# Relay_5x.net
KiCad netlist of a schematic drawn in EasyEDA Pro
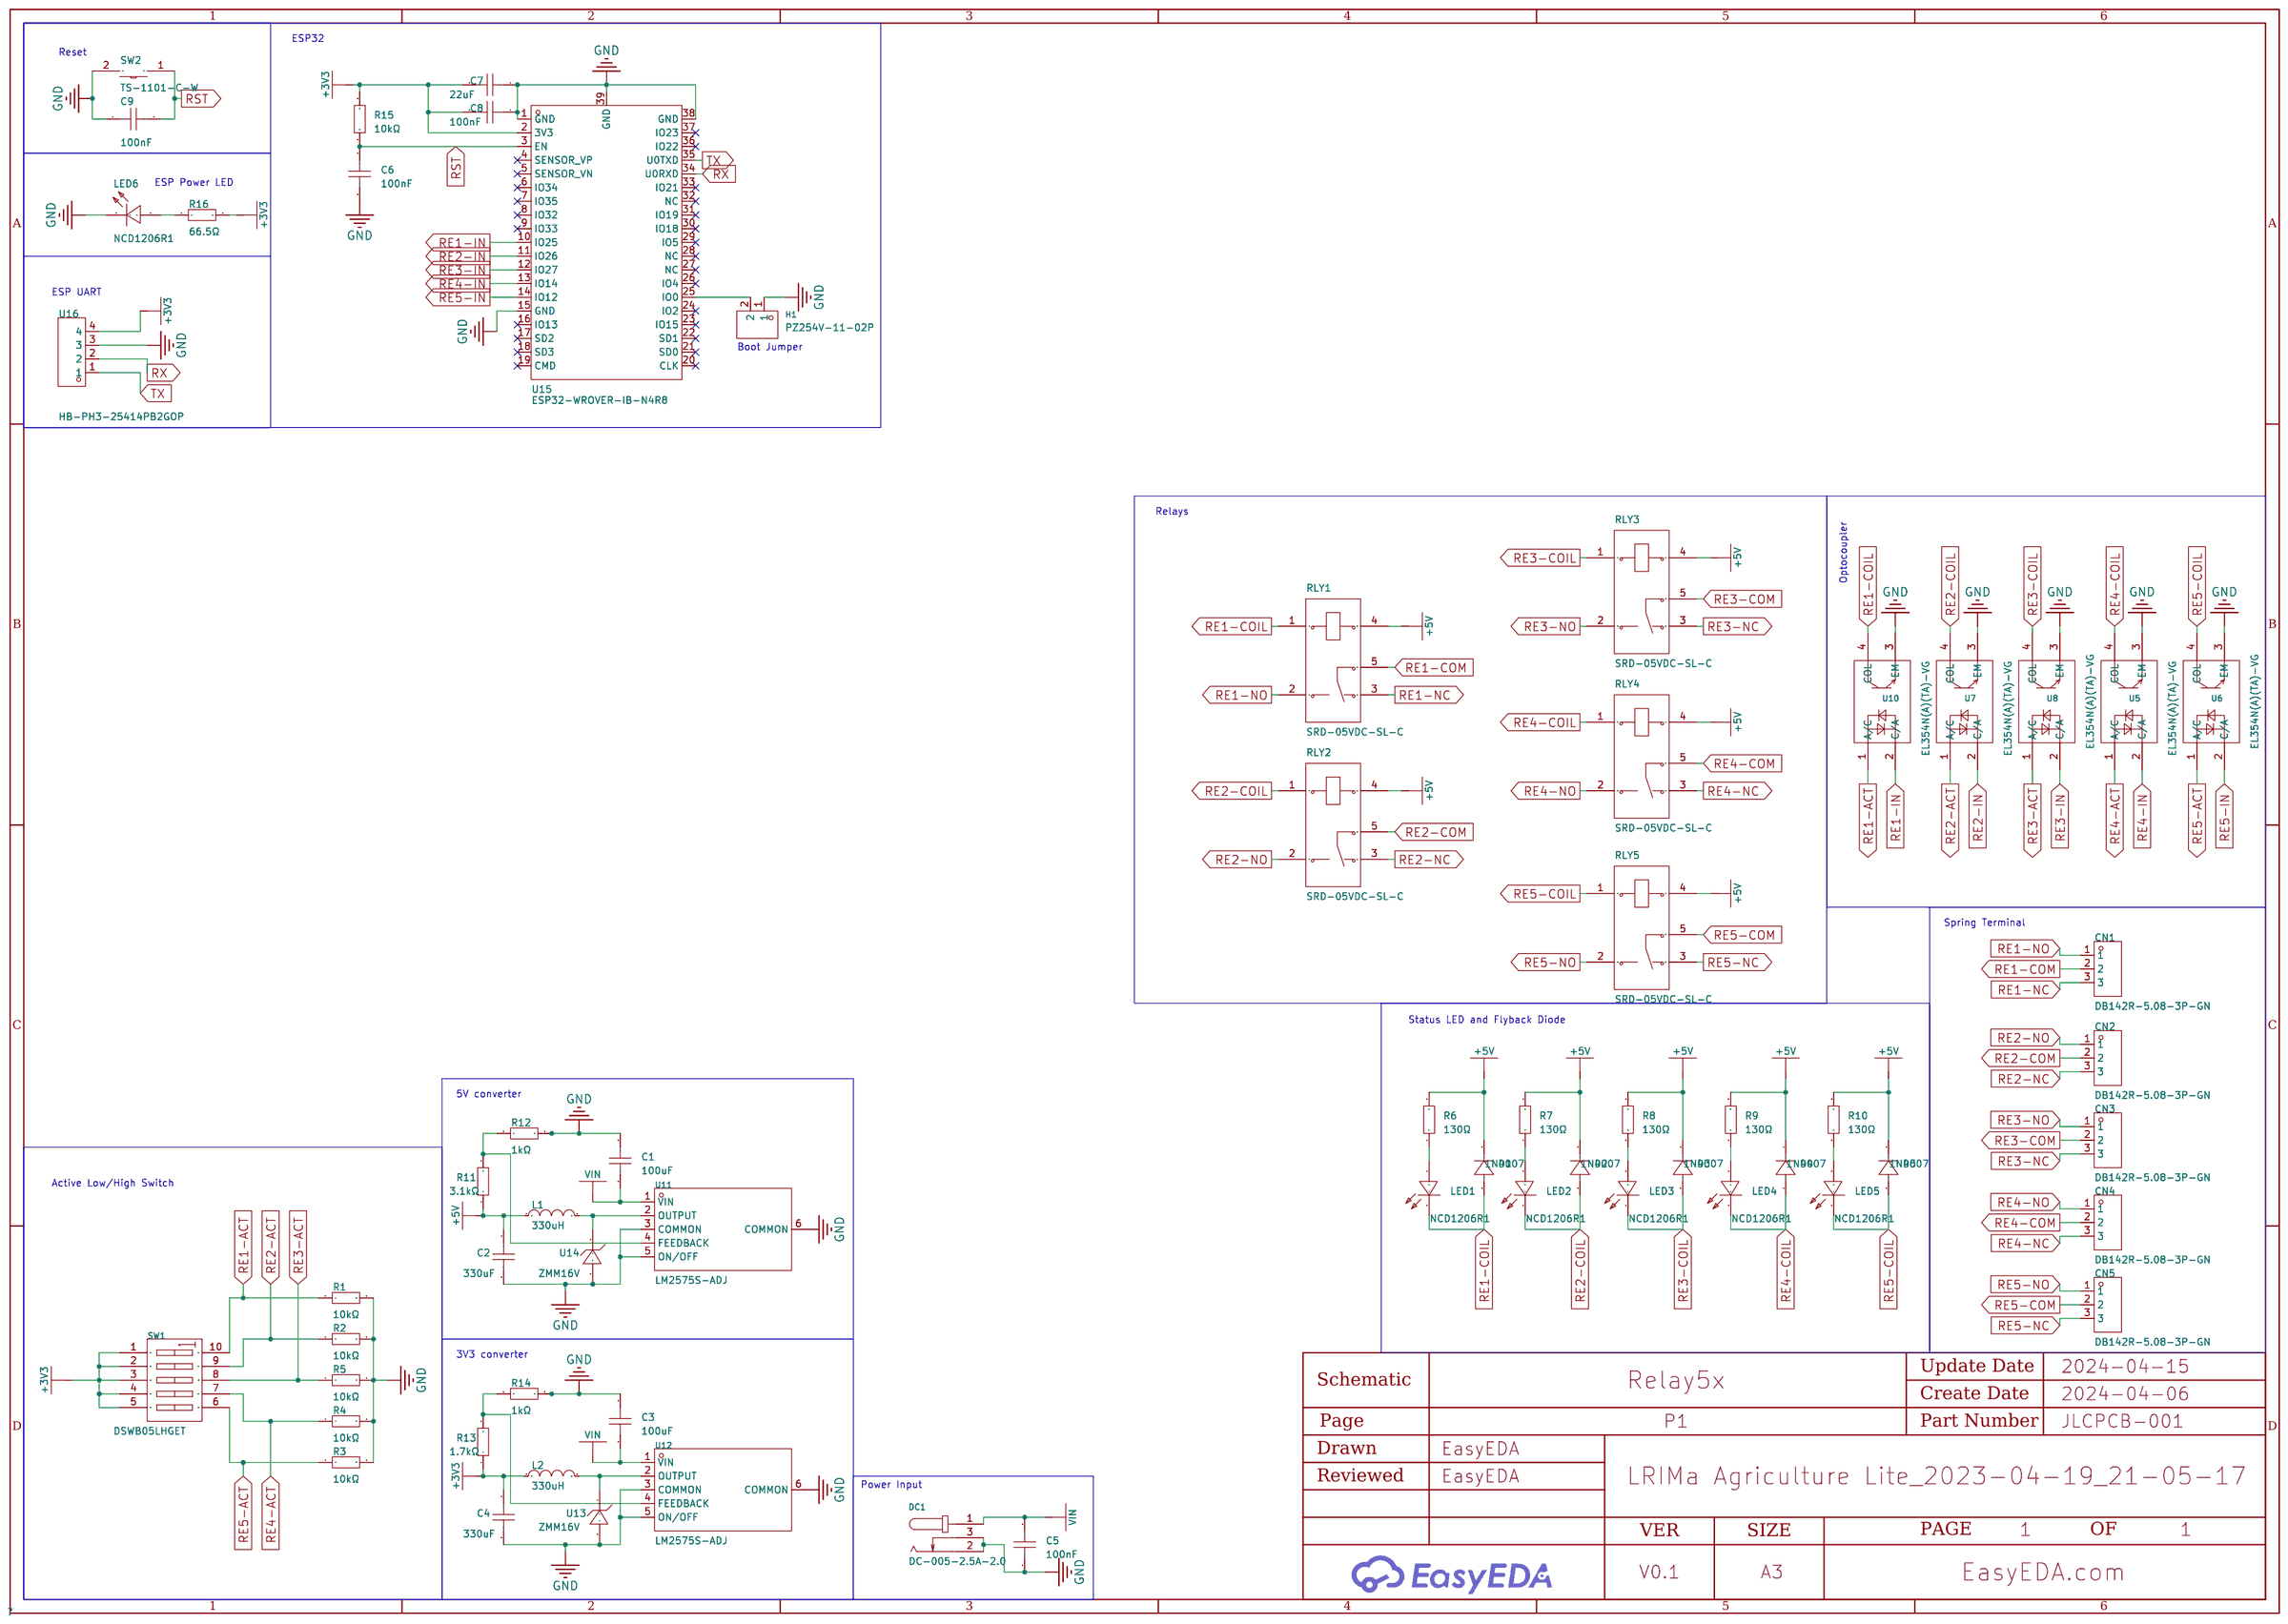
[diagram p0: schematic sheet]

(export (version "E")
  (design (tool "Eeschema 10.0.6"))
  (components
    (comp (ref "C1")
      (value "100uF")
      (fields
        (field (name "Manufacturer Part") "CL31A107MQHNNNE")
        (field (name "Manufacturer") "SAMSUNG(三星)")
      )
      (libsource (lib "easyedapro") (part "CAP"))
    )
    (comp (ref "C2")
      (value "330uF")
      (fields
        (field (name "Manufacturer Part") "GRM32ER60G337ME05L")
        (field (name "Manufacturer") "muRata(村田)")
      )
      (libsource (lib "easyedapro") (part "CAP"))
    )
    (comp (ref "C3")
      (value "100uF")
      (fields
        (field (name "Manufacturer Part") "CL31A107MQHNNNE")
        (field (name "Manufacturer") "SAMSUNG(三星)")
      )
      (libsource (lib "easyedapro") (part "CAP"))
    )
    (comp (ref "C4")
      (value "330uF")
      (fields
        (field (name "Manufacturer Part") "GRM32ER60G337ME05L")
        (field (name "Manufacturer") "muRata(村田)")
      )
      (libsource (lib "easyedapro") (part "CAP"))
    )
    (comp (ref "C5")
      (value "100nF")
      (fields (field (name "Manufacturer Part") "1206B104K101NT") (field (name "Manufacturer") "FH(风华)"))
      (libsource (lib "easyedapro") (part "CAP"))
    )
    (comp (ref "C6")
      (value "100nF")
      (fields (field (name "Manufacturer Part") "1206B104K101NT") (field (name "Manufacturer") "FH(风华)"))
      (libsource (lib "easyedapro") (part "CAP"))
    )
    (comp (ref "C7")
      (value "22uF")
      (fields
        (field (name "Manufacturer Part") "CL31A226KOHNNNE")
        (field (name "Manufacturer") "SAMSUNG(三星)")
      )
      (libsource (lib "easyedapro") (part "CAP"))
    )
    (comp (ref "C8")
      (value "100nF")
      (fields (field (name "Manufacturer Part") "1206B104K101NT") (field (name "Manufacturer") "FH(风华)"))
      (libsource (lib "easyedapro") (part "CAP"))
    )
    (comp (ref "C9")
      (value "100nF")
      (fields (field (name "Manufacturer Part") "1206B104K101NT") (field (name "Manufacturer") "FH(风华)"))
      (libsource (lib "easyedapro") (part "CAP"))
    )
    (comp (ref "CN1")
      (value "DB142R-5.08-3P-GN")
      (footprint "easyedapro:CONN-TH_3P-P5.08_DIBO_DB142R-5.08-3P")
      (fields (field (name "Manufacturer") "DORABO(地博电气)"))
      (libsource (lib "easyedapro") (part "DB142R-5.08-3P"))
    )
    (comp (ref "CN2")
      (value "DB142R-5.08-3P-GN")
      (footprint "easyedapro:CONN-TH_3P-P5.08_DIBO_DB142R-5.08-3P")
      (fields (field (name "Manufacturer") "DORABO(地博电气)"))
      (libsource (lib "easyedapro") (part "DB142R-5.08-3P"))
    )
    (comp (ref "CN3")
      (value "DB142R-5.08-3P-GN")
      (footprint "easyedapro:CONN-TH_3P-P5.08_DIBO_DB142R-5.08-3P")
      (fields (field (name "Manufacturer") "DORABO(地博电气)"))
      (libsource (lib "easyedapro") (part "DB142R-5.08-3P"))
    )
    (comp (ref "CN4")
      (value "DB142R-5.08-3P-GN")
      (footprint "easyedapro:CONN-TH_3P-P5.08_DIBO_DB142R-5.08-3P")
      (fields (field (name "Manufacturer") "DORABO(地博电气)"))
      (libsource (lib "easyedapro") (part "DB142R-5.08-3P"))
    )
    (comp (ref "CN5")
      (value "DB142R-5.08-3P-GN")
      (footprint "easyedapro:CONN-TH_3P-P5.08_DIBO_DB142R-5.08-3P")
      (fields (field (name "Manufacturer") "DORABO(地博电气)"))
      (libsource (lib "easyedapro") (part "DB142R-5.08-3P"))
    )
    (comp (ref "D1")
      (value "1N4007")
      (fields (field (name "Manufacturer") "GOOD-ARK(固锝)"))
      (libsource (lib "easyedapro") (part "D_1N4007"))
    )
    (comp (ref "D2")
      (value "1N4007")
      (fields (field (name "Manufacturer") "GOOD-ARK(固锝)"))
      (libsource (lib "easyedapro") (part "D_1N4007"))
    )
    (comp (ref "D3")
      (value "1N4007")
      (fields (field (name "Manufacturer") "GOOD-ARK(固锝)"))
      (libsource (lib "easyedapro") (part "D_1N4007"))
    )
    (comp (ref "D4")
      (value "1N4007")
      (fields (field (name "Manufacturer") "GOOD-ARK(固锝)"))
      (libsource (lib "easyedapro") (part "D_1N4007"))
    )
    (comp (ref "D5")
      (value "1N4007")
      (fields (field (name "Manufacturer") "GOOD-ARK(固锝)"))
      (libsource (lib "easyedapro") (part "D_1N4007"))
    )
    (comp (ref "DC1")
      (value "DC-005-2.5A-2.0")
      (footprint "easyedapro:CONN-TH_DC-005-2.5A-2.0")
      (fields (field (name "Manufacturer") "XKB Connectivity(中国星坤)"))
      (libsource (lib "easyedapro") (part "DC-005-2.5A-2.0"))
    )
    (comp (ref "H1")
      (value "PZ254V-11-02P")
      (footprint "easyedapro:HDR-TH_2P-P2.54-V-M")
      (fields (field (name "Manufacturer") "XFCN(兴飞)"))
      (libsource (lib "easyedapro") (part "PZ254V-11-02P"))
    )
    (comp (ref "L1")
      (value "330uH")
      (fields (field (name "Manufacturer Part") "NLCV32T-331K-PF") (field (name "Manufacturer") "TDK"))
      (libsource (lib "easyedapro") (part "电感"))
    )
    (comp (ref "L2")
      (value "330uH")
      (fields (field (name "Manufacturer Part") "NLCV32T-331K-PF") (field (name "Manufacturer") "TDK"))
      (libsource (lib "easyedapro") (part "电感"))
    )
    (comp (ref "LED1")
      (value "NCD1206R1")
      (footprint "easyedapro:LED1206-R-RD_RED")
      (fields (field (name "Manufacturer") "国星光电"))
      (libsource (lib "easyedapro") (part "FC-3215HRK-620D"))
    )
    (comp (ref "LED2")
      (value "NCD1206R1")
      (footprint "easyedapro:LED1206-R-RD_RED")
      (fields (field (name "Manufacturer") "国星光电"))
      (libsource (lib "easyedapro") (part "FC-3215HRK-620D"))
    )
    (comp (ref "LED3")
      (value "NCD1206R1")
      (footprint "easyedapro:LED1206-R-RD_RED")
      (fields (field (name "Manufacturer") "国星光电"))
      (libsource (lib "easyedapro") (part "FC-3215HRK-620D"))
    )
    (comp (ref "LED4")
      (value "NCD1206R1")
      (footprint "easyedapro:LED1206-R-RD_RED")
      (fields (field (name "Manufacturer") "国星光电"))
      (libsource (lib "easyedapro") (part "FC-3215HRK-620D"))
    )
    (comp (ref "LED5")
      (value "NCD1206R1")
      (footprint "easyedapro:LED1206-R-RD_RED")
      (fields (field (name "Manufacturer") "国星光电"))
      (libsource (lib "easyedapro") (part "FC-3215HRK-620D"))
    )
    (comp (ref "LED6")
      (value "NCD1206R1")
      (footprint "easyedapro:LED1206-R-RD_RED")
      (fields (field (name "Manufacturer") "国星光电"))
      (libsource (lib "easyedapro") (part "FC-3215HRK-620D"))
    )
    (comp (ref "R1")
      (value "10kΩ")
      (fields
        (field (name "Manufacturer Part") "1206W4F1002T5E")
        (field (name "Manufacturer") "UNI-ROYAL(厚声)")
      )
      (libsource (lib "easyedapro") (part "Res"))
    )
    (comp (ref "R2")
      (value "10kΩ")
      (fields
        (field (name "Manufacturer Part") "1206W4F1002T5E")
        (field (name "Manufacturer") "UNI-ROYAL(厚声)")
      )
      (libsource (lib "easyedapro") (part "Res"))
    )
    (comp (ref "R3")
      (value "10kΩ")
      (fields
        (field (name "Manufacturer Part") "1206W4F1002T5E")
        (field (name "Manufacturer") "UNI-ROYAL(厚声)")
      )
      (libsource (lib "easyedapro") (part "Res"))
    )
    (comp (ref "R4")
      (value "10kΩ")
      (fields
        (field (name "Manufacturer Part") "1206W4F1002T5E")
        (field (name "Manufacturer") "UNI-ROYAL(厚声)")
      )
      (libsource (lib "easyedapro") (part "Res"))
    )
    (comp (ref "R5")
      (value "10kΩ")
      (fields
        (field (name "Manufacturer Part") "1206W4F1002T5E")
        (field (name "Manufacturer") "UNI-ROYAL(厚声)")
      )
      (libsource (lib "easyedapro") (part "Res"))
    )
    (comp (ref "R6")
      (value "130Ω")
      (fields (field (name "Manufacturer Part") "ARG06FTC1300") (field (name "Manufacturer") "Viking(光颉)"))
      (libsource (lib "easyedapro") (part "Res"))
    )
    (comp (ref "R7")
      (value "130Ω")
      (fields (field (name "Manufacturer Part") "ARG06FTC1300") (field (name "Manufacturer") "Viking(光颉)"))
      (libsource (lib "easyedapro") (part "Res"))
    )
    (comp (ref "R8")
      (value "130Ω")
      (fields (field (name "Manufacturer Part") "ARG06FTC1300") (field (name "Manufacturer") "Viking(光颉)"))
      (libsource (lib "easyedapro") (part "Res"))
    )
    (comp (ref "R9")
      (value "130Ω")
      (fields (field (name "Manufacturer Part") "ARG06FTC1300") (field (name "Manufacturer") "Viking(光颉)"))
      (libsource (lib "easyedapro") (part "Res"))
    )
    (comp (ref "R10")
      (value "130Ω")
      (fields (field (name "Manufacturer Part") "ARG06FTC1300") (field (name "Manufacturer") "Viking(光颉)"))
      (libsource (lib "easyedapro") (part "Res"))
    )
    (comp (ref "R11")
      (value "3.1kΩ")
      (fields (field (name "Manufacturer Part") "MF1/8W-3K1±1%-ST52") (field (name "Manufacturer") "VO(翔胜)"))
      (libsource (lib "easyedapro") (part "Res"))
    )
    (comp (ref "R12")
      (value "1kΩ")
      (fields
        (field (name "Manufacturer Part") "1206W4F1001T5E")
        (field (name "Manufacturer") "UNI-ROYAL(厚声)")
      )
      (libsource (lib "easyedapro") (part "Res"))
    )
    (comp (ref "R13")
      (value "1.7kΩ")
      (fields (field (name "Manufacturer Part") "MF1/4W-1K7±1%-ST26") (field (name "Manufacturer") "VO(翔胜)"))
      (libsource (lib "easyedapro") (part "Res"))
    )
    (comp (ref "R14")
      (value "1kΩ")
      (fields
        (field (name "Manufacturer Part") "1206W4F1001T5E")
        (field (name "Manufacturer") "UNI-ROYAL(厚声)")
      )
      (libsource (lib "easyedapro") (part "Res"))
    )
    (comp (ref "R15")
      (value "10kΩ")
      (fields
        (field (name "Manufacturer Part") "1206W4F1002T5E")
        (field (name "Manufacturer") "UNI-ROYAL(厚声)")
      )
      (libsource (lib "easyedapro") (part "Res"))
    )
    (comp (ref "R16")
      (value "66.5Ω")
      (fields
        (field (name "Manufacturer Part") "CR1206F66R5P05Z")
        (field (name "Manufacturer") "EVER OHMS(天二科技)")
      )
      (libsource (lib "easyedapro") (part "Res"))
    )
    (comp (ref "RLY1")
      (value "SRD-05VDC-SL-C")
      (footprint "easyedapro:RELAY-TH_SRD-XXVDC-XL-C")
      (fields (field (name "Manufacturer") "松乐"))
      (libsource (lib "easyedapro") (part "SRD-05VDC-SL-C"))
    )
    (comp (ref "RLY2")
      (value "SRD-05VDC-SL-C")
      (footprint "easyedapro:RELAY-TH_SRD-XXVDC-XL-C")
      (fields (field (name "Manufacturer") "松乐"))
      (libsource (lib "easyedapro") (part "SRD-05VDC-SL-C"))
    )
    (comp (ref "RLY3")
      (value "SRD-05VDC-SL-C")
      (footprint "easyedapro:RELAY-TH_SRD-XXVDC-XL-C")
      (fields (field (name "Manufacturer") "松乐"))
      (libsource (lib "easyedapro") (part "SRD-05VDC-SL-C"))
    )
    (comp (ref "RLY4")
      (value "SRD-05VDC-SL-C")
      (footprint "easyedapro:RELAY-TH_SRD-XXVDC-XL-C")
      (fields (field (name "Manufacturer") "松乐"))
      (libsource (lib "easyedapro") (part "SRD-05VDC-SL-C"))
    )
    (comp (ref "RLY5")
      (value "SRD-05VDC-SL-C")
      (footprint "easyedapro:RELAY-TH_SRD-XXVDC-XL-C")
      (fields (field (name "Manufacturer") "松乐"))
      (libsource (lib "easyedapro") (part "SRD-05VDC-SL-C"))
    )
    (comp (ref "SW1")
      (value "DSWB05LHGET")
      (footprint "easyedapro:SW-TH_DSWB05LHGET")
      (description "Type:平拨,凸起式 Circuit:SPST Number of Positions:5Bit Lead Pitch:2.54mm Operating Life:- Color:Red")
      (fields (field (name "Manufacturer") "YE"))
      (libsource (lib "easyedapro") (part "DSWB05LHGET"))
    )
    (comp (ref "SW2")
      (value "TS-1101-C-W")
      (footprint "easyedapro:SW-SMD_L6.0-W3.3-LS8.0")
      (fields (field (name "Manufacturer") "XKB Connectivity(中国星坤)"))
      (libsource (lib "easyedapro") (part "TS-1101-C-W"))
    )
    (comp (ref "U5")
      (value "EL354N(A)(TA)-VG")
      (footprint "easyedapro:OPTO-SMD-4_L4.4-W4.1-P2.54-LS7.0-TL")
      (fields (field (name "Manufacturer") "EVERLIGHT(亿光)"))
      (libsource (lib "easyedapro") (part "EL354N(A)(TA)-VG"))
    )
    (comp (ref "U6")
      (value "EL354N(A)(TA)-VG")
      (footprint "easyedapro:OPTO-SMD-4_L4.4-W4.1-P2.54-LS7.0-TL")
      (fields (field (name "Manufacturer") "EVERLIGHT(亿光)"))
      (libsource (lib "easyedapro") (part "EL354N(A)(TA)-VG"))
    )
    (comp (ref "U7")
      (value "EL354N(A)(TA)-VG")
      (footprint "easyedapro:OPTO-SMD-4_L4.4-W4.1-P2.54-LS7.0-TL")
      (fields (field (name "Manufacturer") "EVERLIGHT(亿光)"))
      (libsource (lib "easyedapro") (part "EL354N(A)(TA)-VG"))
    )
    (comp (ref "U8")
      (value "EL354N(A)(TA)-VG")
      (footprint "easyedapro:OPTO-SMD-4_L4.4-W4.1-P2.54-LS7.0-TL")
      (fields (field (name "Manufacturer") "EVERLIGHT(亿光)"))
      (libsource (lib "easyedapro") (part "EL354N(A)(TA)-VG"))
    )
    (comp (ref "U10")
      (value "EL354N(A)(TA)-VG")
      (footprint "easyedapro:OPTO-SMD-4_L4.4-W4.1-P2.54-LS7.0-TL")
      (fields (field (name "Manufacturer") "EVERLIGHT(亿光)"))
      (libsource (lib "easyedapro") (part "EL354N(A)(TA)-VG"))
    )
    (comp (ref "U11")
      (value "LM2575S-ADJ")
      (footprint "easyedapro:TO-263-5_L10.2-W8.9-P1.70-BR")
      (fields (field (name "Manufacturer") "Slkor(萨科微)"))
      (libsource (lib "easyedapro") (part "LM2575S-ADJ"))
    )
    (comp (ref "U12")
      (value "LM2575S-ADJ")
      (footprint "easyedapro:TO-263-5_L10.2-W8.9-P1.70-BR")
      (fields (field (name "Manufacturer") "Slkor(萨科微)"))
      (libsource (lib "easyedapro") (part "LM2575S-ADJ"))
    )
    (comp (ref "U13")
      (value "ZMM16V")
      (footprint "easyedapro:LL-34_L3.5-W1.5-RD")
      (fields (field (name "Manufacturer") "YONGYUTAI(永裕泰)"))
      (libsource (lib "easyedapro") (part "ZMM16V"))
    )
    (comp (ref "U14")
      (value "ZMM16V")
      (footprint "easyedapro:LL-34_L3.5-W1.5-RD")
      (fields (field (name "Manufacturer") "YONGYUTAI(永裕泰)"))
      (libsource (lib "easyedapro") (part "ZMM16V"))
    )
    (comp (ref "U15")
      (value "ESP32-WROVER-IB-N4R8")
      (footprint "easyedapro:WIFI-SMD_ESP32-WROVER-IE8MB")
      (fields (field (name "Manufacturer") "ESPRESSIF(乐鑫)"))
      (libsource (lib "easyedapro") (part "ESP32-WROVER-IB-N4R8"))
    )
    (comp (ref "U16")
      (value "HB-PH3-25414PB2GOP")
      (footprint "easyedapro:HDR-TH_4P-P2.54-V-M")
      (fields (field (name "Manufacturer") "HANBO(汉博)"))
      (libsource (lib "easyedapro") (part "HB-PH3-25414PB2GOP"))
    )
  )
  (nets
    (net (code "1") (name "+3V3") (class "Default")
      (node (ref "C4") (pin "1") (pinfunction "1_1") (pintype "input"))
      (node (ref "C7") (pin "2") (pinfunction "2_2") (pintype "input"))
      (node (ref "C8") (pin "2") (pinfunction "2_2") (pintype "input"))
      (node (ref "L2") (pin "1") (pinfunction "1_1") (pintype "input"))
      (node (ref "R13") (pin "1") (pinfunction "1_1") (pintype "input"))
      (node (ref "R15") (pin "2") (pinfunction "2_2") (pintype "input"))
      (node (ref "R16") (pin "2") (pinfunction "2_2") (pintype "input"))
      (node (ref "SW1") (pin "1") (pinfunction "A1_1") (pintype "input"))
      (node (ref "SW1") (pin "2") (pinfunction "A2_2") (pintype "input"))
      (node (ref "SW1") (pin "3") (pinfunction "A3_3") (pintype "input"))
      (node (ref "SW1") (pin "4") (pinfunction "A4_4") (pintype "input"))
      (node (ref "SW1") (pin "5") (pinfunction "A5_5") (pintype "input"))
      (node (ref "U15") (pin "2") (pinfunction "3V3_2") (pintype "unspecified"))
      (node (ref "U16") (pin "4") (pinfunction "4_4") (pintype "unspecified"))
    )
    (net (code "2") (name "+5V") (class "Default")
      (node (ref "C2") (pin "1") (pinfunction "1_1") (pintype "input"))
      (node (ref "D1") (pin "1") (pinfunction "K_1") (pintype "input"))
      (node (ref "D2") (pin "1") (pinfunction "K_1") (pintype "input"))
      (node (ref "D3") (pin "1") (pinfunction "K_1") (pintype "input"))
      (node (ref "D4") (pin "1") (pinfunction "K_1") (pintype "input"))
      (node (ref "D5") (pin "1") (pinfunction "K_1") (pintype "input"))
      (node (ref "L1") (pin "1") (pinfunction "1_1") (pintype "input"))
      (node (ref "R10") (pin "2") (pinfunction "2_2") (pintype "input"))
      (node (ref "R11") (pin "1") (pinfunction "1_1") (pintype "input"))
      (node (ref "R6") (pin "2") (pinfunction "2_2") (pintype "input"))
      (node (ref "R7") (pin "2") (pinfunction "2_2") (pintype "input"))
      (node (ref "R8") (pin "2") (pinfunction "2_2") (pintype "input"))
      (node (ref "R9") (pin "2") (pinfunction "2_2") (pintype "input"))
      (node (ref "RLY1") (pin "4") (pinfunction "4_4") (pintype "input"))
      (node (ref "RLY2") (pin "4") (pinfunction "4_4") (pintype "input"))
      (node (ref "RLY3") (pin "4") (pinfunction "4_4") (pintype "input"))
      (node (ref "RLY4") (pin "4") (pinfunction "4_4") (pintype "input"))
      (node (ref "RLY5") (pin "4") (pinfunction "4_4") (pintype "input"))
    )
    (net (code "3") (name "GND") (class "Default")
      (node (ref "C1") (pin "1") (pinfunction "1_1") (pintype "input"))
      (node (ref "C2") (pin "2") (pinfunction "2_2") (pintype "input"))
      (node (ref "C3") (pin "1") (pinfunction "1_1") (pintype "input"))
      (node (ref "C4") (pin "2") (pinfunction "2_2") (pintype "input"))
      (node (ref "C5") (pin "2") (pinfunction "2_2") (pintype "input"))
      (node (ref "C6") (pin "2") (pinfunction "2_2") (pintype "input"))
      (node (ref "C7") (pin "1") (pinfunction "1_1") (pintype "input"))
      (node (ref "C8") (pin "1") (pinfunction "1_1") (pintype "input"))
      (node (ref "C9") (pin "1") (pinfunction "1_1") (pintype "input"))
      (node (ref "DC1") (pin "2") (pinfunction "2_2") (pintype "input"))
      (node (ref "DC1") (pin "3") (pinfunction "3_3") (pintype "input"))
      (node (ref "H1") (pin "1") (pinfunction "1_1") (pintype "input"))
      (node (ref "LED6") (pin "2") (pinfunction "K_2") (pintype "unspecified"))
      (node (ref "R1") (pin "2") (pinfunction "2_2") (pintype "input"))
      (node (ref "R12") (pin "1") (pinfunction "1_1") (pintype "input"))
      (node (ref "R14") (pin "1") (pinfunction "1_1") (pintype "input"))
      (node (ref "R2") (pin "2") (pinfunction "2_2") (pintype "input"))
      (node (ref "R3") (pin "2") (pinfunction "2_2") (pintype "input"))
      (node (ref "R4") (pin "2") (pinfunction "2_2") (pintype "input"))
      (node (ref "R5") (pin "2") (pinfunction "2_2") (pintype "input"))
      (node (ref "SW2") (pin "2") (pinfunction "2_2") (pintype "unspecified"))
      (node (ref "U10") (pin "3") (pinfunction "EM_3") (pintype "input"))
      (node (ref "U11") (pin "3") (pinfunction "COMMON_3") (pintype "input"))
      (node (ref "U11") (pin "5") (pinfunction "ON/OFF_5") (pintype "input"))
      (node (ref "U11") (pin "6") (pinfunction "COMMON_6") (pintype "input"))
      (node (ref "U12") (pin "3") (pinfunction "COMMON_3") (pintype "input"))
      (node (ref "U12") (pin "5") (pinfunction "ON/OFF_5") (pintype "input"))
      (node (ref "U12") (pin "6") (pinfunction "COMMON_6") (pintype "input"))
      (node (ref "U13") (pin "2") (pinfunction "A_2") (pintype "unspecified"))
      (node (ref "U14") (pin "2") (pinfunction "A_2") (pintype "unspecified"))
      (node (ref "U15") (pin "1") (pinfunction "GND_1") (pintype "unspecified"))
      (node (ref "U15") (pin "15") (pinfunction "GND_15") (pintype "unspecified"))
      (node (ref "U15") (pin "38") (pinfunction "GND_38") (pintype "unspecified"))
      (node (ref "U15") (pin "39") (pinfunction "GND_39") (pintype "unspecified"))
      (node (ref "U16") (pin "3") (pinfunction "3_3") (pintype "unspecified"))
      (node (ref "U5") (pin "3") (pinfunction "EM_3") (pintype "input"))
      (node (ref "U6") (pin "3") (pinfunction "EM_3") (pintype "input"))
      (node (ref "U7") (pin "3") (pinfunction "EM_3") (pintype "input"))
      (node (ref "U8") (pin "3") (pinfunction "EM_3") (pintype "input"))
    )
    (net (code "4") (name "Net-(LED1-A)") (class "Default")
      (node (ref "LED1") (pin "1") (pinfunction "A_1") (pintype "unspecified"))
      (node (ref "R6") (pin "1") (pinfunction "1_1") (pintype "input"))
    )
    (net (code "5") (name "Net-(LED2-A)") (class "Default")
      (node (ref "LED2") (pin "1") (pinfunction "A_1") (pintype "unspecified"))
      (node (ref "R7") (pin "1") (pinfunction "1_1") (pintype "input"))
    )
    (net (code "6") (name "Net-(LED3-A)") (class "Default")
      (node (ref "LED3") (pin "1") (pinfunction "A_1") (pintype "unspecified"))
      (node (ref "R8") (pin "1") (pinfunction "1_1") (pintype "input"))
    )
    (net (code "7") (name "Net-(LED4-A)") (class "Default")
      (node (ref "LED4") (pin "1") (pinfunction "A_1") (pintype "unspecified"))
      (node (ref "R9") (pin "1") (pinfunction "1_1") (pintype "input"))
    )
    (net (code "8") (name "Net-(LED5-A)") (class "Default")
      (node (ref "LED5") (pin "1") (pinfunction "A_1") (pintype "unspecified"))
      (node (ref "R10") (pin "1") (pinfunction "1_1") (pintype "input"))
    )
    (net (code "9") (name "Net-(LED6-A)") (class "Default")
      (node (ref "LED6") (pin "1") (pinfunction "A_1") (pintype "unspecified"))
      (node (ref "R16") (pin "1") (pinfunction "1_1") (pintype "input"))
    )
    (net (code "10") (name "Net-(U11-FEEDBACK)") (class "Default")
      (node (ref "R11") (pin "2") (pinfunction "2_2") (pintype "input"))
      (node (ref "R12") (pin "2") (pinfunction "2_2") (pintype "input"))
      (node (ref "U11") (pin "4") (pinfunction "FEEDBACK_4") (pintype "input"))
    )
    (net (code "11") (name "Net-(U11-OUTPUT)") (class "Default")
      (node (ref "L1") (pin "2") (pinfunction "2_2") (pintype "input"))
      (node (ref "U11") (pin "2") (pinfunction "OUTPUT_2") (pintype "input"))
      (node (ref "U14") (pin "1") (pinfunction "K_1") (pintype "unspecified"))
    )
    (net (code "12") (name "Net-(U12-FEEDBACK)") (class "Default")
      (node (ref "R13") (pin "2") (pinfunction "2_2") (pintype "input"))
      (node (ref "R14") (pin "2") (pinfunction "2_2") (pintype "input"))
      (node (ref "U12") (pin "4") (pinfunction "FEEDBACK_4") (pintype "input"))
    )
    (net (code "13") (name "Net-(U12-OUTPUT)") (class "Default")
      (node (ref "L2") (pin "2") (pinfunction "2_2") (pintype "input"))
      (node (ref "U12") (pin "2") (pinfunction "OUTPUT_2") (pintype "input"))
      (node (ref "U13") (pin "1") (pinfunction "K_1") (pintype "unspecified"))
    )
    (net (code "14") (name "Net-(U15-IO0)") (class "Default")
      (node (ref "H1") (pin "2") (pinfunction "2_2") (pintype "input"))
      (node (ref "U15") (pin "25") (pinfunction "IO0_25") (pintype "unspecified"))
    )
    (net (code "15") (name "RE1-ACT") (class "Default")
      (node (ref "R1") (pin "1") (pinfunction "1_1") (pintype "input"))
      (node (ref "SW1") (pin "10") (pinfunction "B1_10") (pintype "input"))
      (node (ref "U10") (pin "1") (pinfunction "A/C_1") (pintype "input"))
    )
    (net (code "16") (name "RE1-COIL") (class "Default")
      (node (ref "D1") (pin "2") (pinfunction "A_2") (pintype "input"))
      (node (ref "LED1") (pin "2") (pinfunction "K_2") (pintype "unspecified"))
      (node (ref "RLY1") (pin "1") (pinfunction "1_1") (pintype "input"))
      (node (ref "U10") (pin "4") (pinfunction "COL_4") (pintype "input"))
    )
    (net (code "17") (name "RE1-COM") (class "Default")
      (node (ref "CN1") (pin "2") (pinfunction "2_2") (pintype "unspecified"))
      (node (ref "RLY1") (pin "5") (pinfunction "5_5") (pintype "input"))
    )
    (net (code "18") (name "RE1-IN") (class "Default")
      (node (ref "U10") (pin "2") (pinfunction "C/A_2") (pintype "input"))
      (node (ref "U15") (pin "10") (pinfunction "IO25_10") (pintype "unspecified"))
    )
    (net (code "19") (name "RE1-NC") (class "Default")
      (node (ref "CN1") (pin "3") (pinfunction "3_3") (pintype "unspecified"))
      (node (ref "RLY1") (pin "3") (pinfunction "3_3") (pintype "input"))
    )
    (net (code "20") (name "RE1-NO") (class "Default")
      (node (ref "CN1") (pin "1") (pinfunction "1_1") (pintype "unspecified"))
      (node (ref "RLY1") (pin "2") (pinfunction "2_2") (pintype "input"))
    )
    (net (code "21") (name "RE2-ACT") (class "Default")
      (node (ref "R2") (pin "1") (pinfunction "1_1") (pintype "input"))
      (node (ref "SW1") (pin "9") (pinfunction "B2_9") (pintype "input"))
      (node (ref "U7") (pin "1") (pinfunction "A/C_1") (pintype "input"))
    )
    (net (code "22") (name "RE2-COIL") (class "Default")
      (node (ref "D2") (pin "2") (pinfunction "A_2") (pintype "input"))
      (node (ref "LED2") (pin "2") (pinfunction "K_2") (pintype "unspecified"))
      (node (ref "RLY2") (pin "1") (pinfunction "1_1") (pintype "input"))
      (node (ref "U7") (pin "4") (pinfunction "COL_4") (pintype "input"))
    )
    (net (code "23") (name "RE2-COM") (class "Default")
      (node (ref "CN2") (pin "2") (pinfunction "2_2") (pintype "unspecified"))
      (node (ref "RLY2") (pin "5") (pinfunction "5_5") (pintype "input"))
    )
    (net (code "24") (name "RE2-IN") (class "Default")
      (node (ref "U15") (pin "11") (pinfunction "IO26_11") (pintype "unspecified"))
      (node (ref "U7") (pin "2") (pinfunction "C/A_2") (pintype "input"))
    )
    (net (code "25") (name "RE2-NC") (class "Default")
      (node (ref "CN2") (pin "3") (pinfunction "3_3") (pintype "unspecified"))
      (node (ref "RLY2") (pin "3") (pinfunction "3_3") (pintype "input"))
    )
    (net (code "26") (name "RE2-NO") (class "Default")
      (node (ref "CN2") (pin "1") (pinfunction "1_1") (pintype "unspecified"))
      (node (ref "RLY2") (pin "2") (pinfunction "2_2") (pintype "input"))
    )
    (net (code "27") (name "RE3-ACT") (class "Default")
      (node (ref "R5") (pin "1") (pinfunction "1_1") (pintype "input"))
      (node (ref "SW1") (pin "8") (pinfunction "B3_8") (pintype "input"))
      (node (ref "U8") (pin "1") (pinfunction "A/C_1") (pintype "input"))
    )
    (net (code "28") (name "RE3-COIL") (class "Default")
      (node (ref "D3") (pin "2") (pinfunction "A_2") (pintype "input"))
      (node (ref "LED3") (pin "2") (pinfunction "K_2") (pintype "unspecified"))
      (node (ref "RLY3") (pin "1") (pinfunction "1_1") (pintype "input"))
      (node (ref "U8") (pin "4") (pinfunction "COL_4") (pintype "input"))
    )
    (net (code "29") (name "RE3-COM") (class "Default")
      (node (ref "CN3") (pin "2") (pinfunction "2_2") (pintype "unspecified"))
      (node (ref "RLY3") (pin "5") (pinfunction "5_5") (pintype "input"))
    )
    (net (code "30") (name "RE3-IN") (class "Default")
      (node (ref "U15") (pin "12") (pinfunction "IO27_12") (pintype "unspecified"))
      (node (ref "U8") (pin "2") (pinfunction "C/A_2") (pintype "input"))
    )
    (net (code "31") (name "RE3-NC") (class "Default")
      (node (ref "CN3") (pin "3") (pinfunction "3_3") (pintype "unspecified"))
      (node (ref "RLY3") (pin "3") (pinfunction "3_3") (pintype "input"))
    )
    (net (code "32") (name "RE3-NO") (class "Default")
      (node (ref "CN3") (pin "1") (pinfunction "1_1") (pintype "unspecified"))
      (node (ref "RLY3") (pin "2") (pinfunction "2_2") (pintype "input"))
    )
    (net (code "33") (name "RE4-ACT") (class "Default")
      (node (ref "R4") (pin "1") (pinfunction "1_1") (pintype "input"))
      (node (ref "SW1") (pin "7") (pinfunction "B4_7") (pintype "input"))
      (node (ref "U5") (pin "1") (pinfunction "A/C_1") (pintype "input"))
    )
    (net (code "34") (name "RE4-COIL") (class "Default")
      (node (ref "D4") (pin "2") (pinfunction "A_2") (pintype "input"))
      (node (ref "LED4") (pin "2") (pinfunction "K_2") (pintype "unspecified"))
      (node (ref "RLY4") (pin "1") (pinfunction "1_1") (pintype "input"))
      (node (ref "U5") (pin "4") (pinfunction "COL_4") (pintype "input"))
    )
    (net (code "35") (name "RE4-COM") (class "Default")
      (node (ref "CN4") (pin "2") (pinfunction "2_2") (pintype "unspecified"))
      (node (ref "RLY4") (pin "5") (pinfunction "5_5") (pintype "input"))
    )
    (net (code "36") (name "RE4-IN") (class "Default")
      (node (ref "U15") (pin "13") (pinfunction "IO14_13") (pintype "unspecified"))
      (node (ref "U5") (pin "2") (pinfunction "C/A_2") (pintype "input"))
    )
    (net (code "37") (name "RE4-NC") (class "Default")
      (node (ref "CN4") (pin "3") (pinfunction "3_3") (pintype "unspecified"))
      (node (ref "RLY4") (pin "3") (pinfunction "3_3") (pintype "input"))
    )
    (net (code "38") (name "RE4-NO") (class "Default")
      (node (ref "CN4") (pin "1") (pinfunction "1_1") (pintype "unspecified"))
      (node (ref "RLY4") (pin "2") (pinfunction "2_2") (pintype "input"))
    )
    (net (code "39") (name "RE5-ACT") (class "Default")
      (node (ref "R3") (pin "1") (pinfunction "1_1") (pintype "input"))
      (node (ref "SW1") (pin "6") (pinfunction "B5_6") (pintype "input"))
      (node (ref "U6") (pin "1") (pinfunction "A/C_1") (pintype "input"))
    )
    (net (code "40") (name "RE5-COIL") (class "Default")
      (node (ref "D5") (pin "2") (pinfunction "A_2") (pintype "input"))
      (node (ref "LED5") (pin "2") (pinfunction "K_2") (pintype "unspecified"))
      (node (ref "RLY5") (pin "1") (pinfunction "1_1") (pintype "input"))
      (node (ref "U6") (pin "4") (pinfunction "COL_4") (pintype "input"))
    )
    (net (code "41") (name "RE5-COM") (class "Default")
      (node (ref "CN5") (pin "2") (pinfunction "2_2") (pintype "unspecified"))
      (node (ref "RLY5") (pin "5") (pinfunction "5_5") (pintype "input"))
    )
    (net (code "42") (name "RE5-IN") (class "Default")
      (node (ref "U15") (pin "14") (pinfunction "IO12_14") (pintype "unspecified"))
      (node (ref "U6") (pin "2") (pinfunction "C/A_2") (pintype "input"))
    )
    (net (code "43") (name "RE5-NC") (class "Default")
      (node (ref "CN5") (pin "3") (pinfunction "3_3") (pintype "unspecified"))
      (node (ref "RLY5") (pin "3") (pinfunction "3_3") (pintype "input"))
    )
    (net (code "44") (name "RE5-NO") (class "Default")
      (node (ref "CN5") (pin "1") (pinfunction "1_1") (pintype "unspecified"))
      (node (ref "RLY5") (pin "2") (pinfunction "2_2") (pintype "input"))
    )
    (net (code "45") (name "RST") (class "Default")
      (node (ref "C6") (pin "1") (pinfunction "1_1") (pintype "input"))
      (node (ref "C9") (pin "2") (pinfunction "2_2") (pintype "input"))
      (node (ref "R15") (pin "1") (pinfunction "1_1") (pintype "input"))
      (node (ref "SW2") (pin "1") (pinfunction "1_1") (pintype "unspecified"))
      (node (ref "U15") (pin "3") (pinfunction "EN_3") (pintype "unspecified"))
    )
    (net (code "46") (name "RX") (class "Default")
      (node (ref "U15") (pin "34") (pinfunction "U0RXD_34") (pintype "unspecified"))
      (node (ref "U16") (pin "2") (pinfunction "2_2") (pintype "unspecified"))
    )
    (net (code "47") (name "TX") (class "Default")
      (node (ref "U15") (pin "35") (pinfunction "U0TXD_35") (pintype "unspecified"))
      (node (ref "U16") (pin "1") (pinfunction "1_1") (pintype "unspecified"))
    )
    (net (code "48") (name "VIN") (class "Default")
      (node (ref "C1") (pin "2") (pinfunction "2_2") (pintype "input"))
      (node (ref "C3") (pin "2") (pinfunction "2_2") (pintype "input"))
      (node (ref "C5") (pin "1") (pinfunction "1_1") (pintype "input"))
      (node (ref "DC1") (pin "1") (pinfunction "1_1") (pintype "input"))
      (node (ref "U11") (pin "1") (pinfunction "VIN_1") (pintype "input"))
      (node (ref "U12") (pin "1") (pinfunction "VIN_1") (pintype "input"))
    )
    (net (code "49") (name "unconnected-(U15-CLK-Pad20)") (class "Default")
      (node (ref "U15") (pin "20") (pinfunction "CLK_20") (pintype "unspecified+no_connect"))
    )
    (net (code "50") (name "unconnected-(U15-CMD-Pad19)") (class "Default")
      (node (ref "U15") (pin "19") (pinfunction "CMD_19") (pintype "unspecified+no_connect"))
    )
    (net (code "51") (name "unconnected-(U15-IO2-Pad24)") (class "Default")
      (node (ref "U15") (pin "24") (pinfunction "IO2_24") (pintype "unspecified+no_connect"))
    )
    (net (code "52") (name "unconnected-(U15-IO4-Pad26)") (class "Default")
      (node (ref "U15") (pin "26") (pinfunction "IO4_26") (pintype "unspecified+no_connect"))
    )
    (net (code "53") (name "unconnected-(U15-IO5-Pad29)") (class "Default")
      (node (ref "U15") (pin "29") (pinfunction "IO5_29") (pintype "unspecified+no_connect"))
    )
    (net (code "54") (name "unconnected-(U15-IO13-Pad16)") (class "Default")
      (node (ref "U15") (pin "16") (pinfunction "IO13_16") (pintype "unspecified+no_connect"))
    )
    (net (code "55") (name "unconnected-(U15-IO15-Pad23)") (class "Default")
      (node (ref "U15") (pin "23") (pinfunction "IO15_23") (pintype "unspecified+no_connect"))
    )
    (net (code "56") (name "unconnected-(U15-IO18-Pad30)") (class "Default")
      (node (ref "U15") (pin "30") (pinfunction "IO18_30") (pintype "unspecified+no_connect"))
    )
    (net (code "57") (name "unconnected-(U15-IO19-Pad31)") (class "Default")
      (node (ref "U15") (pin "31") (pinfunction "IO19_31") (pintype "unspecified+no_connect"))
    )
    (net (code "58") (name "unconnected-(U15-IO21-Pad33)") (class "Default")
      (node (ref "U15") (pin "33") (pinfunction "IO21_33") (pintype "unspecified+no_connect"))
    )
    (net (code "59") (name "unconnected-(U15-IO22-Pad36)") (class "Default")
      (node (ref "U15") (pin "36") (pinfunction "IO22_36") (pintype "unspecified+no_connect"))
    )
    (net (code "60") (name "unconnected-(U15-IO23-Pad37)") (class "Default")
      (node (ref "U15") (pin "37") (pinfunction "IO23_37") (pintype "unspecified+no_connect"))
    )
    (net (code "61") (name "unconnected-(U15-IO32-Pad8)") (class "Default")
      (node (ref "U15") (pin "8") (pinfunction "IO32_8") (pintype "unspecified+no_connect"))
    )
    (net (code "62") (name "unconnected-(U15-IO33-Pad9)") (class "Default")
      (node (ref "U15") (pin "9") (pinfunction "IO33_9") (pintype "unspecified+no_connect"))
    )
    (net (code "63") (name "unconnected-(U15-IO34-Pad6)") (class "Default")
      (node (ref "U15") (pin "6") (pinfunction "IO34_6") (pintype "unspecified+no_connect"))
    )
    (net (code "64") (name "unconnected-(U15-IO35-Pad7)") (class "Default")
      (node (ref "U15") (pin "7") (pinfunction "IO35_7") (pintype "unspecified+no_connect"))
    )
    (net (code "65") (name "unconnected-(U15-NC-Pad27)") (class "Default")
      (node (ref "U15") (pin "27") (pinfunction "NC_27") (pintype "unspecified+no_connect"))
    )
    (net (code "66") (name "unconnected-(U15-NC-Pad28)") (class "Default")
      (node (ref "U15") (pin "28") (pinfunction "NC_28") (pintype "unspecified+no_connect"))
    )
    (net (code "67") (name "unconnected-(U15-NC-Pad32)") (class "Default")
      (node (ref "U15") (pin "32") (pinfunction "NC_32") (pintype "unspecified+no_connect"))
    )
    (net (code "68") (name "unconnected-(U15-SD0-Pad21)") (class "Default")
      (node (ref "U15") (pin "21") (pinfunction "SD0_21") (pintype "unspecified+no_connect"))
    )
    (net (code "69") (name "unconnected-(U15-SD1-Pad22)") (class "Default")
      (node (ref "U15") (pin "22") (pinfunction "SD1_22") (pintype "unspecified+no_connect"))
    )
    (net (code "70") (name "unconnected-(U15-SD2-Pad17)") (class "Default")
      (node (ref "U15") (pin "17") (pinfunction "SD2_17") (pintype "unspecified+no_connect"))
    )
    (net (code "71") (name "unconnected-(U15-SD3-Pad18)") (class "Default")
      (node (ref "U15") (pin "18") (pinfunction "SD3_18") (pintype "unspecified+no_connect"))
    )
    (net (code "72") (name "unconnected-(U15-SENSOR_VN-Pad5)") (class "Default")
      (node (ref "U15") (pin "5") (pinfunction "SENSOR_VN_5") (pintype "unspecified+no_connect"))
    )
    (net (code "73") (name "unconnected-(U15-SENSOR_VP-Pad4)") (class "Default")
      (node (ref "U15") (pin "4") (pinfunction "SENSOR_VP_4") (pintype "unspecified+no_connect"))
    )
  )
)
